# Buzzer.net
KiCad netlist of a schematic drawn in Altium Designer
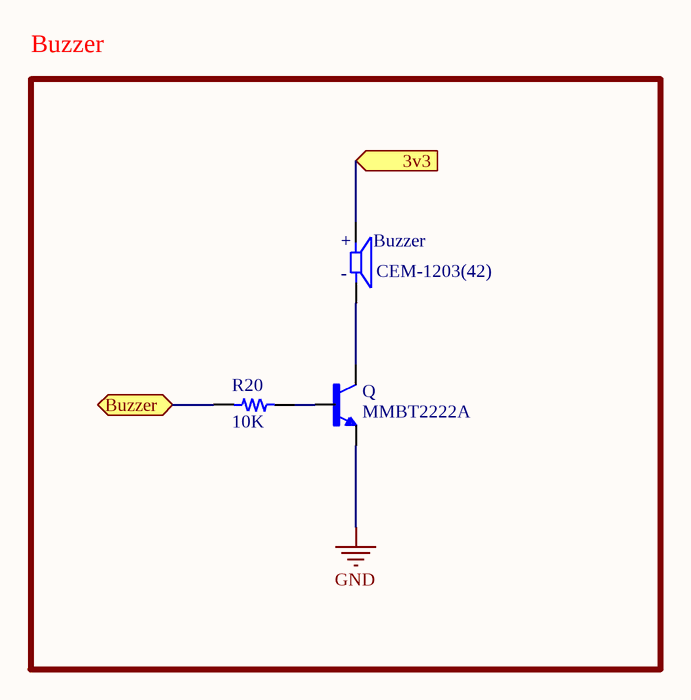
[diagram p0: Buzzer.SchDoc]

(export (version "E")
  (design (tool "Eeschema 10.0.6"))
  (components
    (comp (ref "Buzzer")
      (value "CEM-1203(42)")
      (footprint "CUI_CEM-1203(42)")
      (description "12 mm, 3.5 V, 85 dB, Through Hole, Magnetic Audio Transducer Buzzer")
      (fields (field (name "MF") "CUI Devices"))
      (libsource (lib "Buzzer 12mm") (part "CEM-1203(42)"))
    )
    (comp (ref "Q")
      (value "MMBT2222A")
      (footprint "SOT23")
      (description "Bipolar _BJT_ Transistor NPN 40V 600mA 270MHz 350mW Surface Mount SOT-23-3")
      (fields (field (name "MF") "STMicroelectronics"))
      (libsource (lib "MMBT2222A") (part "MMBT2222A"))
    )
    (comp (ref "R20")
      (value "10K")
      (footprint "RES 0805_2012")
      (description "SMT Resistor")
      (libsource (lib "Resistor") (part "Res 0805"))
    )
  )
  (nets
    (net (code "1") (name "/3v3") (class "Default")
      (node (ref "Buzzer") (pin "P") (pinfunction "P_P") (pintype "passive"))
    )
    (net (code "2") (name "/Buzzer") (class "Default")
      (node (ref "R20") (pin "1") (pinfunction "1_1") (pintype "passive"))
    )
    (net (code "3") (name "GND") (class "Default")
      (node (ref "Q") (pin "2") (pinfunction "E_2") (pintype "passive"))
    )
    (net (code "4") (name "Net-(Q-B)") (class "Default")
      (node (ref "Q") (pin "1") (pinfunction "B_1") (pintype "passive"))
      (node (ref "R20") (pin "2") (pinfunction "2_2") (pintype "passive"))
    )
    (net (code "5") (name "Net-(Q-C)") (class "Default")
      (node (ref "Buzzer") (pin "N") (pinfunction "N_N") (pintype "passive"))
      (node (ref "Q") (pin "3") (pinfunction "C_3") (pintype "passive"))
    )
  )
)
